# CO2Monitor_V0_1.net
KiCad netlist of a schematic drawn in EAGLE
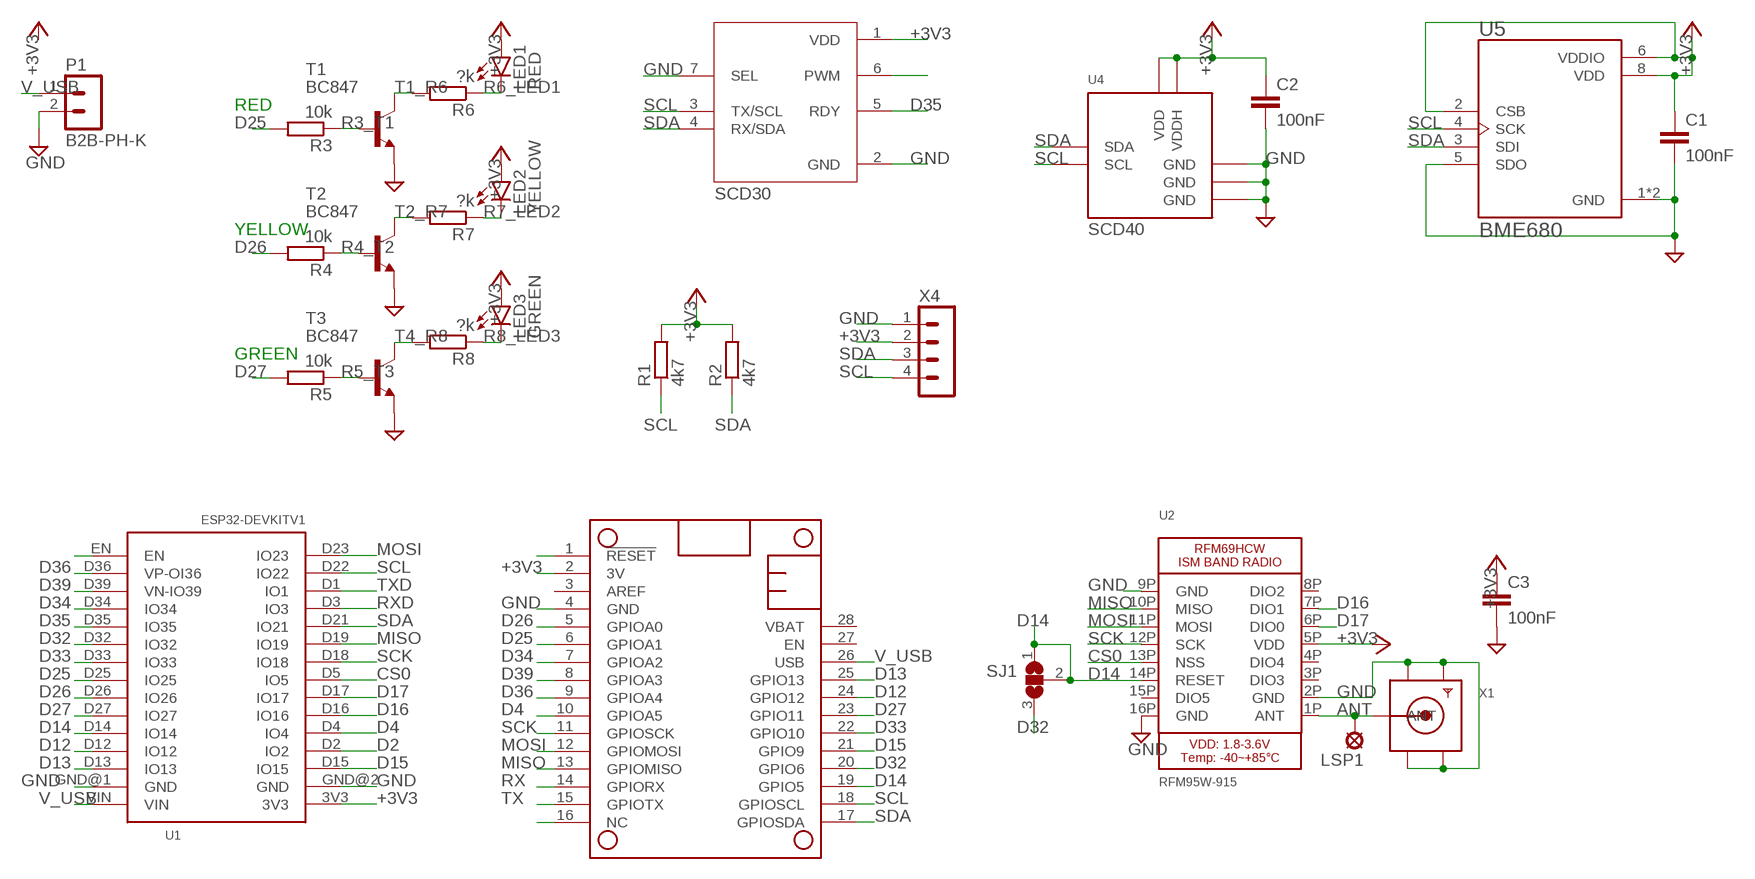
[diagram p0: schematic, sheet 1]

(export (version "E")
  (design (tool "Eeschema 10.0.6"))
  (components
    (comp (ref "C1")
      (value "100nF")
      (footprint "eagle-import:C0805")
      (libsource (lib "eagle-import") (part "C-EUC0805"))
    )
    (comp (ref "C2")
      (value "100nF")
      (footprint "eagle-import:C0805")
      (libsource (lib "eagle-import") (part "C-EUC0805"))
    )
    (comp (ref "C3")
      (value "100nF")
      (footprint "eagle-import:C0805")
      (libsource (lib "eagle-import") (part "C-EUC0805"))
    )
    (comp (ref "LED1")
      (value "RED")
      (footprint "eagle-import:LED5MM")
      (libsource (lib "eagle-import") (part "LED5MM"))
    )
    (comp (ref "LED2")
      (value "YELLOW")
      (footprint "eagle-import:LED5MM")
      (libsource (lib "eagle-import") (part "LED5MM"))
    )
    (comp (ref "LED3")
      (value "GREEN")
      (footprint "eagle-import:LED5MM")
      (libsource (lib "eagle-import") (part "LED5MM"))
    )
    (comp (ref "LSP1")
      (value "LSP10")
      (footprint "eagle-import:LSP10")
      (libsource (lib "eagle-import") (part "LSP10"))
    )
    (comp (ref "MS1")
      (value "FEATHERWING_FOOTPRINTFOOTPRINT")
      (footprint "eagle-import:FEATHERWING_FOOTPRINT")
      (libsource (lib "eagle-import") (part "FEATHERWING_FOOTPRINTFOOTPRINT"))
    )
    (comp (ref "P1")
      (value "B2B-PH-K")
      (footprint "eagle-import:B2B-PH-K")
      (libsource (lib "eagle-import") (part "B2B-PH-K"))
    )
    (comp (ref "R1")
      (value "4k7")
      (footprint "eagle-import:R0805")
      (libsource (lib "eagle-import") (part "R-EU_R0805"))
    )
    (comp (ref "R2")
      (value "4k7")
      (footprint "eagle-import:R0805")
      (libsource (lib "eagle-import") (part "R-EU_R0805"))
    )
    (comp (ref "R3")
      (value "10k")
      (footprint "eagle-import:R0805")
      (libsource (lib "eagle-import") (part "R-EU_R0805"))
    )
    (comp (ref "R4")
      (value "10k")
      (footprint "eagle-import:R0805")
      (libsource (lib "eagle-import") (part "R-EU_R0805"))
    )
    (comp (ref "R5")
      (value "10k")
      (footprint "eagle-import:R0805")
      (libsource (lib "eagle-import") (part "R-EU_R0805"))
    )
    (comp (ref "R6")
      (value "?k")
      (footprint "eagle-import:R0805")
      (libsource (lib "eagle-import") (part "R-EU_R0805"))
    )
    (comp (ref "R7")
      (value "?k")
      (footprint "eagle-import:R0805")
      (libsource (lib "eagle-import") (part "R-EU_R0805"))
    )
    (comp (ref "R8")
      (value "?k")
      (footprint "eagle-import:R0805")
      (libsource (lib "eagle-import") (part "R-EU_R0805"))
    )
    (comp (ref "SJ1")
      (value "SJ2W")
      (footprint "eagle-import:SJ_2")
      (libsource (lib "eagle-import") (part "SJ2W"))
    )
    (comp (ref "T1")
      (value "BC847")
      (footprint "eagle-import:SOT23")
      (libsource (lib "eagle-import") (part "BC847"))
    )
    (comp (ref "T2")
      (value "BC847")
      (footprint "eagle-import:SOT23")
      (libsource (lib "eagle-import") (part "BC847"))
    )
    (comp (ref "T3")
      (value "BC847")
      (footprint "eagle-import:SOT23")
      (libsource (lib "eagle-import") (part "BC847"))
    )
    (comp (ref "U1")
      (value "ESP32DEVKITV1")
      (footprint "eagle-import:ESP32-DEVKITV1")
      (libsource (lib "eagle-import") (part "ESP32DEVKITV1"))
    )
    (comp (ref "U2")
      (value "RFM95W-915")
      (footprint "eagle-import:MICROBUILDER_RFMHCW_SMT")
      (libsource (lib "eagle-import") (part "MICROBUILDER_RFM69HCW_SMT"))
    )
    (comp (ref "U3")
      (value "SCD30")
      (footprint "eagle-import:MODULE_SCD30")
      (fields (field (name "MF") "Sensirion AG"))
      (libsource (lib "eagle-import") (part "SCD30"))
    )
    (comp (ref "U4")
      (value "SCD40")
      (footprint "eagle-import:SCD40")
      (libsource (lib "eagle-import") (part "SCD40"))
    )
    (comp (ref "U5")
      (value "BME680")
      (footprint "eagle-import:PSON80P300X300X100-8N")
      (fields (field (name "MF") "Bosch Sensortec"))
      (libsource (lib "eagle-import") (part "BME680"))
    )
    (comp (ref "X1")
      (value "SMACONNECTOR_EDGE_UFL")
      (footprint "eagle-import:SMA_EDGELAUNCH_UFL")
      (libsource (lib "eagle-import") (part "SMACONNECTOR_EDGE_UFL"))
    )
    (comp (ref "X4")
      (value "B4B-PH-K")
      (footprint "eagle-import:B4B-PH-K")
      (libsource (lib "eagle-import") (part "B4B-PH-K"))
    )
  )
  (nets
    (net (code "1") (name "+3V3") (class "Default")
      (node (ref "C1") (pin "1") (pinfunction "1_1") (pintype "passive"))
      (node (ref "C2") (pin "1") (pinfunction "1_1") (pintype "passive"))
      (node (ref "C3") (pin "1") (pinfunction "1_1") (pintype "passive"))
      (node (ref "LED1") (pin "A") (pinfunction "A_A") (pintype "passive"))
      (node (ref "LED2") (pin "A") (pinfunction "A_A") (pintype "passive"))
      (node (ref "LED3") (pin "A") (pinfunction "A_A") (pintype "passive"))
      (node (ref "MS1") (pin "2") (pinfunction "3V_2") (pintype "power_in"))
      (node (ref "R1") (pin "2") (pinfunction "2_2") (pintype "passive"))
      (node (ref "R2") (pin "2") (pinfunction "2_2") (pintype "passive"))
      (node (ref "U1") (pin "3V3") (pinfunction "3V3_3V3") (pintype "bidirectional"))
      (node (ref "U2") (pin "5P") (pinfunction "VDD_5P") (pintype "power_in"))
      (node (ref "U3") (pin "1") (pinfunction "VDD_1") (pintype "power_in"))
      (node (ref "U4") (pin "P$19") (pinfunction "VDDH_P$19") (pintype "power_in"))
      (node (ref "U4") (pin "P$7") (pinfunction "VDD_P$7") (pintype "power_in"))
      (node (ref "U5") (pin "2") (pinfunction "CSB_2") (pintype "input"))
      (node (ref "U5") (pin "6") (pinfunction "VDDIO_6") (pintype "power_in"))
      (node (ref "U5") (pin "8") (pinfunction "VDD_8") (pintype "power_in"))
      (node (ref "X4") (pin "2") (pinfunction "2_2") (pintype "passive"))
    )
    (net (code "2") (name "/ANT") (class "Default")
      (node (ref "LSP1") (pin "MP") (pinfunction "MP_MP") (pintype "passive"))
      (node (ref "U2") (pin "1P") (pinfunction "ANT_1P") (pintype "bidirectional"))
      (node (ref "X1") (pin "P") (pinfunction "ANT_P") (pintype "bidirectional"))
    )
    (net (code "3") (name "/CS0") (class "Default")
      (node (ref "U1") (pin "D5") (pinfunction "IO5_D5") (pintype "bidirectional"))
      (node (ref "U2") (pin "13P") (pinfunction "NSS_13P") (pintype "input"))
    )
    (net (code "4") (name "/D2") (class "Default")
      (node (ref "U1") (pin "D2") (pinfunction "IO2_D2") (pintype "bidirectional"))
    )
    (net (code "5") (name "/D4") (class "Default")
      (node (ref "MS1") (pin "10") (pinfunction "GPIOA5_10") (pintype "bidirectional"))
      (node (ref "U1") (pin "D4") (pinfunction "IO4_D4") (pintype "bidirectional"))
    )
    (net (code "6") (name "/D12") (class "Default")
      (node (ref "MS1") (pin "24") (pinfunction "GPIO12_24") (pintype "bidirectional"))
      (node (ref "U1") (pin "D12") (pinfunction "IO12_D12") (pintype "bidirectional"))
    )
    (net (code "7") (name "/D13") (class "Default")
      (node (ref "MS1") (pin "25") (pinfunction "GPIO13_25") (pintype "bidirectional"))
      (node (ref "U1") (pin "D13") (pinfunction "IO13_D13") (pintype "bidirectional"))
    )
    (net (code "8") (name "/D14") (class "Default")
      (node (ref "MS1") (pin "19") (pinfunction "GPIO5_19") (pintype "bidirectional"))
      (node (ref "SJ1") (pin "1") (pinfunction "1_1") (pintype "passive"))
      (node (ref "SJ1") (pin "2") (pinfunction "2_2") (pintype "passive"))
      (node (ref "U1") (pin "D14") (pinfunction "IO14_D14") (pintype "bidirectional"))
      (node (ref "U2") (pin "14P") (pinfunction "RESET_14P") (pintype "input"))
    )
    (net (code "9") (name "/D15") (class "Default")
      (node (ref "MS1") (pin "21") (pinfunction "GPIO9_21") (pintype "bidirectional"))
      (node (ref "U1") (pin "D15") (pinfunction "IO15_D15") (pintype "bidirectional"))
    )
    (net (code "10") (name "/D16") (class "Default")
      (node (ref "U1") (pin "D16") (pinfunction "IO16_D16") (pintype "bidirectional"))
      (node (ref "U2") (pin "7P") (pinfunction "DIO1_7P") (pintype "bidirectional"))
    )
    (net (code "11") (name "/D17") (class "Default")
      (node (ref "U1") (pin "D17") (pinfunction "IO17_D17") (pintype "bidirectional"))
      (node (ref "U2") (pin "6P") (pinfunction "DIO0_6P") (pintype "bidirectional"))
    )
    (net (code "12") (name "/D25") (class "Default")
      (node (ref "MS1") (pin "6") (pinfunction "GPIOA1_6") (pintype "bidirectional"))
      (node (ref "R3") (pin "2") (pinfunction "2_2") (pintype "passive"))
      (node (ref "U1") (pin "D25") (pinfunction "IO25_D25") (pintype "bidirectional"))
    )
    (net (code "13") (name "/D26") (class "Default")
      (node (ref "MS1") (pin "5") (pinfunction "GPIOA0_5") (pintype "bidirectional"))
      (node (ref "R4") (pin "2") (pinfunction "2_2") (pintype "passive"))
      (node (ref "U1") (pin "D26") (pinfunction "IO26_D26") (pintype "bidirectional"))
    )
    (net (code "14") (name "/D27") (class "Default")
      (node (ref "MS1") (pin "23") (pinfunction "GPIO11_23") (pintype "bidirectional"))
      (node (ref "R5") (pin "2") (pinfunction "2_2") (pintype "passive"))
      (node (ref "U1") (pin "D27") (pinfunction "IO27_D27") (pintype "bidirectional"))
    )
    (net (code "15") (name "/D32") (class "Default")
      (node (ref "MS1") (pin "20") (pinfunction "GPIO6_20") (pintype "bidirectional"))
      (node (ref "SJ1") (pin "3") (pinfunction "3_3") (pintype "passive"))
      (node (ref "U1") (pin "D32") (pinfunction "IO32_D32") (pintype "bidirectional"))
    )
    (net (code "16") (name "/D33") (class "Default")
      (node (ref "MS1") (pin "22") (pinfunction "GPIO10_22") (pintype "bidirectional"))
      (node (ref "U1") (pin "D33") (pinfunction "IO33_D33") (pintype "bidirectional"))
    )
    (net (code "17") (name "/D34") (class "Default")
      (node (ref "MS1") (pin "7") (pinfunction "GPIOA2_7") (pintype "bidirectional"))
      (node (ref "U1") (pin "D34") (pinfunction "IO34_D34") (pintype "bidirectional"))
    )
    (net (code "18") (name "/D35") (class "Default")
      (node (ref "U1") (pin "D35") (pinfunction "IO35_D35") (pintype "bidirectional"))
      (node (ref "U3") (pin "5") (pinfunction "RDY_5") (pintype "bidirectional"))
    )
    (net (code "19") (name "/D36") (class "Default")
      (node (ref "MS1") (pin "9") (pinfunction "GPIOA4_9") (pintype "bidirectional"))
      (node (ref "U1") (pin "D36") (pinfunction "VP-OI36_D36") (pintype "bidirectional"))
    )
    (net (code "20") (name "/D39") (class "Default")
      (node (ref "MS1") (pin "8") (pinfunction "GPIOA3_8") (pintype "bidirectional"))
      (node (ref "U1") (pin "D39") (pinfunction "VN-IO39_D39") (pintype "bidirectional"))
    )
    (net (code "21") (name "/MISO") (class "Default")
      (node (ref "MS1") (pin "13") (pinfunction "GPIOMISO_13") (pintype "bidirectional"))
      (node (ref "U1") (pin "D19") (pinfunction "IO19_D19") (pintype "bidirectional"))
      (node (ref "U2") (pin "10P") (pinfunction "MISO_10P") (pintype "output"))
    )
    (net (code "22") (name "/MOSI") (class "Default")
      (node (ref "MS1") (pin "12") (pinfunction "GPIOMOSI_12") (pintype "bidirectional"))
      (node (ref "U1") (pin "D23") (pinfunction "IO23_D23") (pintype "bidirectional"))
      (node (ref "U2") (pin "11P") (pinfunction "MOSI_11P") (pintype "input"))
    )
    (net (code "23") (name "/R3_T1") (class "Default")
      (node (ref "R3") (pin "1") (pinfunction "1_1") (pintype "passive"))
      (node (ref "T1") (pin "1") (pinfunction "B_1") (pintype "passive"))
    )
    (net (code "24") (name "/R4_T2") (class "Default")
      (node (ref "R4") (pin "1") (pinfunction "1_1") (pintype "passive"))
      (node (ref "T2") (pin "1") (pinfunction "B_1") (pintype "passive"))
    )
    (net (code "25") (name "/R5_T3") (class "Default")
      (node (ref "R5") (pin "1") (pinfunction "1_1") (pintype "passive"))
      (node (ref "T3") (pin "1") (pinfunction "B_1") (pintype "passive"))
    )
    (net (code "26") (name "/R6_LED1") (class "Default")
      (node (ref "LED1") (pin "K") (pinfunction "C_K") (pintype "passive"))
      (node (ref "R6") (pin "1") (pinfunction "1_1") (pintype "passive"))
    )
    (net (code "27") (name "/R7_LED2") (class "Default")
      (node (ref "LED2") (pin "K") (pinfunction "C_K") (pintype "passive"))
      (node (ref "R7") (pin "1") (pinfunction "1_1") (pintype "passive"))
    )
    (net (code "28") (name "/R8_LED3") (class "Default")
      (node (ref "LED3") (pin "K") (pinfunction "C_K") (pintype "passive"))
      (node (ref "R8") (pin "1") (pinfunction "1_1") (pintype "passive"))
    )
    (net (code "29") (name "/RX") (class "Default")
      (node (ref "MS1") (pin "14") (pinfunction "GPIORX_14") (pintype "bidirectional"))
    )
    (net (code "30") (name "/RXD") (class "Default")
      (node (ref "U1") (pin "D3") (pinfunction "IO3_D3") (pintype "bidirectional"))
    )
    (net (code "31") (name "/SCK") (class "Default")
      (node (ref "MS1") (pin "11") (pinfunction "GPIOSCK_11") (pintype "bidirectional"))
      (node (ref "U1") (pin "D18") (pinfunction "IO18_D18") (pintype "bidirectional"))
      (node (ref "U2") (pin "12P") (pinfunction "SCK_12P") (pintype "input"))
    )
    (net (code "32") (name "/SCL") (class "Default")
      (node (ref "MS1") (pin "18") (pinfunction "GPIOSCL_18") (pintype "bidirectional"))
      (node (ref "R1") (pin "1") (pinfunction "1_1") (pintype "passive"))
      (node (ref "U1") (pin "D22") (pinfunction "IO22_D22") (pintype "bidirectional"))
      (node (ref "U3") (pin "3") (pinfunction "TX/SCL_3") (pintype "bidirectional"))
      (node (ref "U4") (pin "P$9") (pinfunction "SCL_P$9") (pintype "bidirectional"))
      (node (ref "U5") (pin "4") (pinfunction "SCK_4") (pintype "input"))
      (node (ref "X4") (pin "4") (pinfunction "4_4") (pintype "passive"))
    )
    (net (code "33") (name "/SDA") (class "Default")
      (node (ref "MS1") (pin "17") (pinfunction "GPIOSDA_17") (pintype "bidirectional"))
      (node (ref "R2") (pin "1") (pinfunction "1_1") (pintype "passive"))
      (node (ref "U1") (pin "D21") (pinfunction "IO21_D21") (pintype "bidirectional"))
      (node (ref "U3") (pin "4") (pinfunction "RX/SDA_4") (pintype "bidirectional"))
      (node (ref "U4") (pin "P$10") (pinfunction "SDA_P$10") (pintype "bidirectional"))
      (node (ref "U5") (pin "3") (pinfunction "SDI_3") (pintype "bidirectional"))
      (node (ref "X4") (pin "3") (pinfunction "3_3") (pintype "passive"))
    )
    (net (code "34") (name "/T1_R6") (class "Default")
      (node (ref "R6") (pin "2") (pinfunction "2_2") (pintype "passive"))
      (node (ref "T1") (pin "3") (pinfunction "C_3") (pintype "passive"))
    )
    (net (code "35") (name "/T2_R7") (class "Default")
      (node (ref "R7") (pin "2") (pinfunction "2_2") (pintype "passive"))
      (node (ref "T2") (pin "3") (pinfunction "C_3") (pintype "passive"))
    )
    (net (code "36") (name "/T4_R8") (class "Default")
      (node (ref "R8") (pin "2") (pinfunction "2_2") (pintype "passive"))
      (node (ref "T3") (pin "3") (pinfunction "C_3") (pintype "passive"))
    )
    (net (code "37") (name "/TX") (class "Default")
      (node (ref "MS1") (pin "15") (pinfunction "GPIOTX_15") (pintype "bidirectional"))
    )
    (net (code "38") (name "/TXD") (class "Default")
      (node (ref "U1") (pin "D1") (pinfunction "IO1_D1") (pintype "bidirectional"))
    )
    (net (code "39") (name "/VBAT") (class "Default")
      (node (ref "MS1") (pin "28") (pinfunction "VBAT_28") (pintype "power_in"))
    )
    (net (code "40") (name "/V_USB") (class "Default")
      (node (ref "MS1") (pin "26") (pinfunction "USB_26") (pintype "power_in"))
      (node (ref "P1") (pin "1") (pinfunction "1_1") (pintype "passive"))
      (node (ref "U1") (pin "VIN") (pinfunction "VIN_VIN") (pintype "bidirectional"))
    )
    (net (code "41") (name "GND") (class "Default")
      (node (ref "C1") (pin "2") (pinfunction "2_2") (pintype "passive"))
      (node (ref "C2") (pin "2") (pinfunction "2_2") (pintype "passive"))
      (node (ref "C3") (pin "2") (pinfunction "2_2") (pintype "passive"))
      (node (ref "MS1") (pin "4") (pinfunction "GND_4") (pintype "power_in"))
      (node (ref "P1") (pin "2") (pinfunction "2_2") (pintype "passive"))
      (node (ref "T1") (pin "2") (pinfunction "E_2") (pintype "passive"))
      (node (ref "T2") (pin "2") (pinfunction "E_2") (pintype "passive"))
      (node (ref "T3") (pin "2") (pinfunction "E_2") (pintype "passive"))
      (node (ref "U1") (pin "GND@1") (pinfunction "GND_GND@1") (pintype "bidirectional"))
      (node (ref "U1") (pin "GND@2") (pinfunction "GND_GND@2") (pintype "bidirectional"))
      (node (ref "U2") (pin "16P") (pinfunction "GND_16P") (pintype "power_in"))
      (node (ref "U2") (pin "2P") (pinfunction "GND_2P") (pintype "power_in"))
      (node (ref "U2") (pin "9P") (pinfunction "GND_9P") (pintype "power_in"))
      (node (ref "U3") (pin "2") (pinfunction "GND_2") (pintype "power_in"))
      (node (ref "U3") (pin "7") (pinfunction "SEL_7") (pintype "input"))
      (node (ref "U4") (pin "P$20") (pinfunction "GND_P$20") (pintype "power_in"))
      (node (ref "U4") (pin "P$21") (pinfunction "GND_P$21") (pintype "power_in"))
      (node (ref "U4") (pin "P$6") (pinfunction "GND_P$6") (pintype "power_in"))
      (node (ref "U5") (pin "1") (pinfunction "GND_1") (pintype "power_in"))
      (node (ref "U5") (pin "5") (pinfunction "SDO_5") (pintype "bidirectional"))
      (node (ref "U5") (pin "7") (pinfunction "GND_7") (pintype "power_in"))
      (node (ref "X1") (pin "GND@1") (pinfunction "GND1_GND@1") (pintype "power_in"))
      (node (ref "X1") (pin "GND@2") (pinfunction "GND2_GND@2") (pintype "power_in"))
      (node (ref "X1") (pin "GND@3") (pinfunction "GND3_GND@3") (pintype "power_in"))
      (node (ref "X1") (pin "GND@4") (pinfunction "GND4_GND@4") (pintype "power_in"))
      (node (ref "X4") (pin "1") (pinfunction "1_1") (pintype "passive"))
    )
    (net (code "42") (name "unconnected-(MS1-AREF-Pad3)") (class "Default")
      (node (ref "MS1") (pin "3") (pinfunction "AREF_3") (pintype "passive"))
    )
    (net (code "43") (name "unconnected-(MS1-EN-Pad27)") (class "Default")
      (node (ref "MS1") (pin "27") (pinfunction "EN_27") (pintype "passive"))
    )
    (net (code "44") (name "unconnected-(MS1-NC-Pad16)") (class "Default")
      (node (ref "MS1") (pin "16") (pinfunction "NC_16") (pintype "passive"))
    )
    (net (code "45") (name "unconnected-(MS1-~{RESET}-Pad1)") (class "Default")
      (node (ref "MS1") (pin "1") (pinfunction "~{RESET}_1") (pintype "input"))
    )
    (net (code "46") (name "unconnected-(U1-PadEN)") (class "Default")
      (node (ref "U1") (pin "EN") (pinfunction "EN_EN") (pintype "bidirectional"))
    )
    (net (code "47") (name "unconnected-(U2-DIO2-Pad8P)") (class "Default")
      (node (ref "U2") (pin "8P") (pinfunction "DIO2_8P") (pintype "bidirectional"))
    )
    (net (code "48") (name "unconnected-(U2-DIO3-Pad3P)") (class "Default")
      (node (ref "U2") (pin "3P") (pinfunction "DIO3_3P") (pintype "bidirectional"))
    )
    (net (code "49") (name "unconnected-(U2-DIO4-Pad4P)") (class "Default")
      (node (ref "U2") (pin "4P") (pinfunction "DIO4_4P") (pintype "bidirectional"))
    )
    (net (code "50") (name "unconnected-(U2-DIO5-Pad15P)") (class "Default")
      (node (ref "U2") (pin "15P") (pinfunction "DIO5_15P") (pintype "bidirectional"))
    )
    (net (code "51") (name "unconnected-(U3-PWM-Pad6)") (class "Default")
      (node (ref "U3") (pin "6") (pinfunction "PWM_6") (pintype "output"))
    )
  )
)
